# diodes.net
KiCad netlist of a schematic drawn in EAGLE
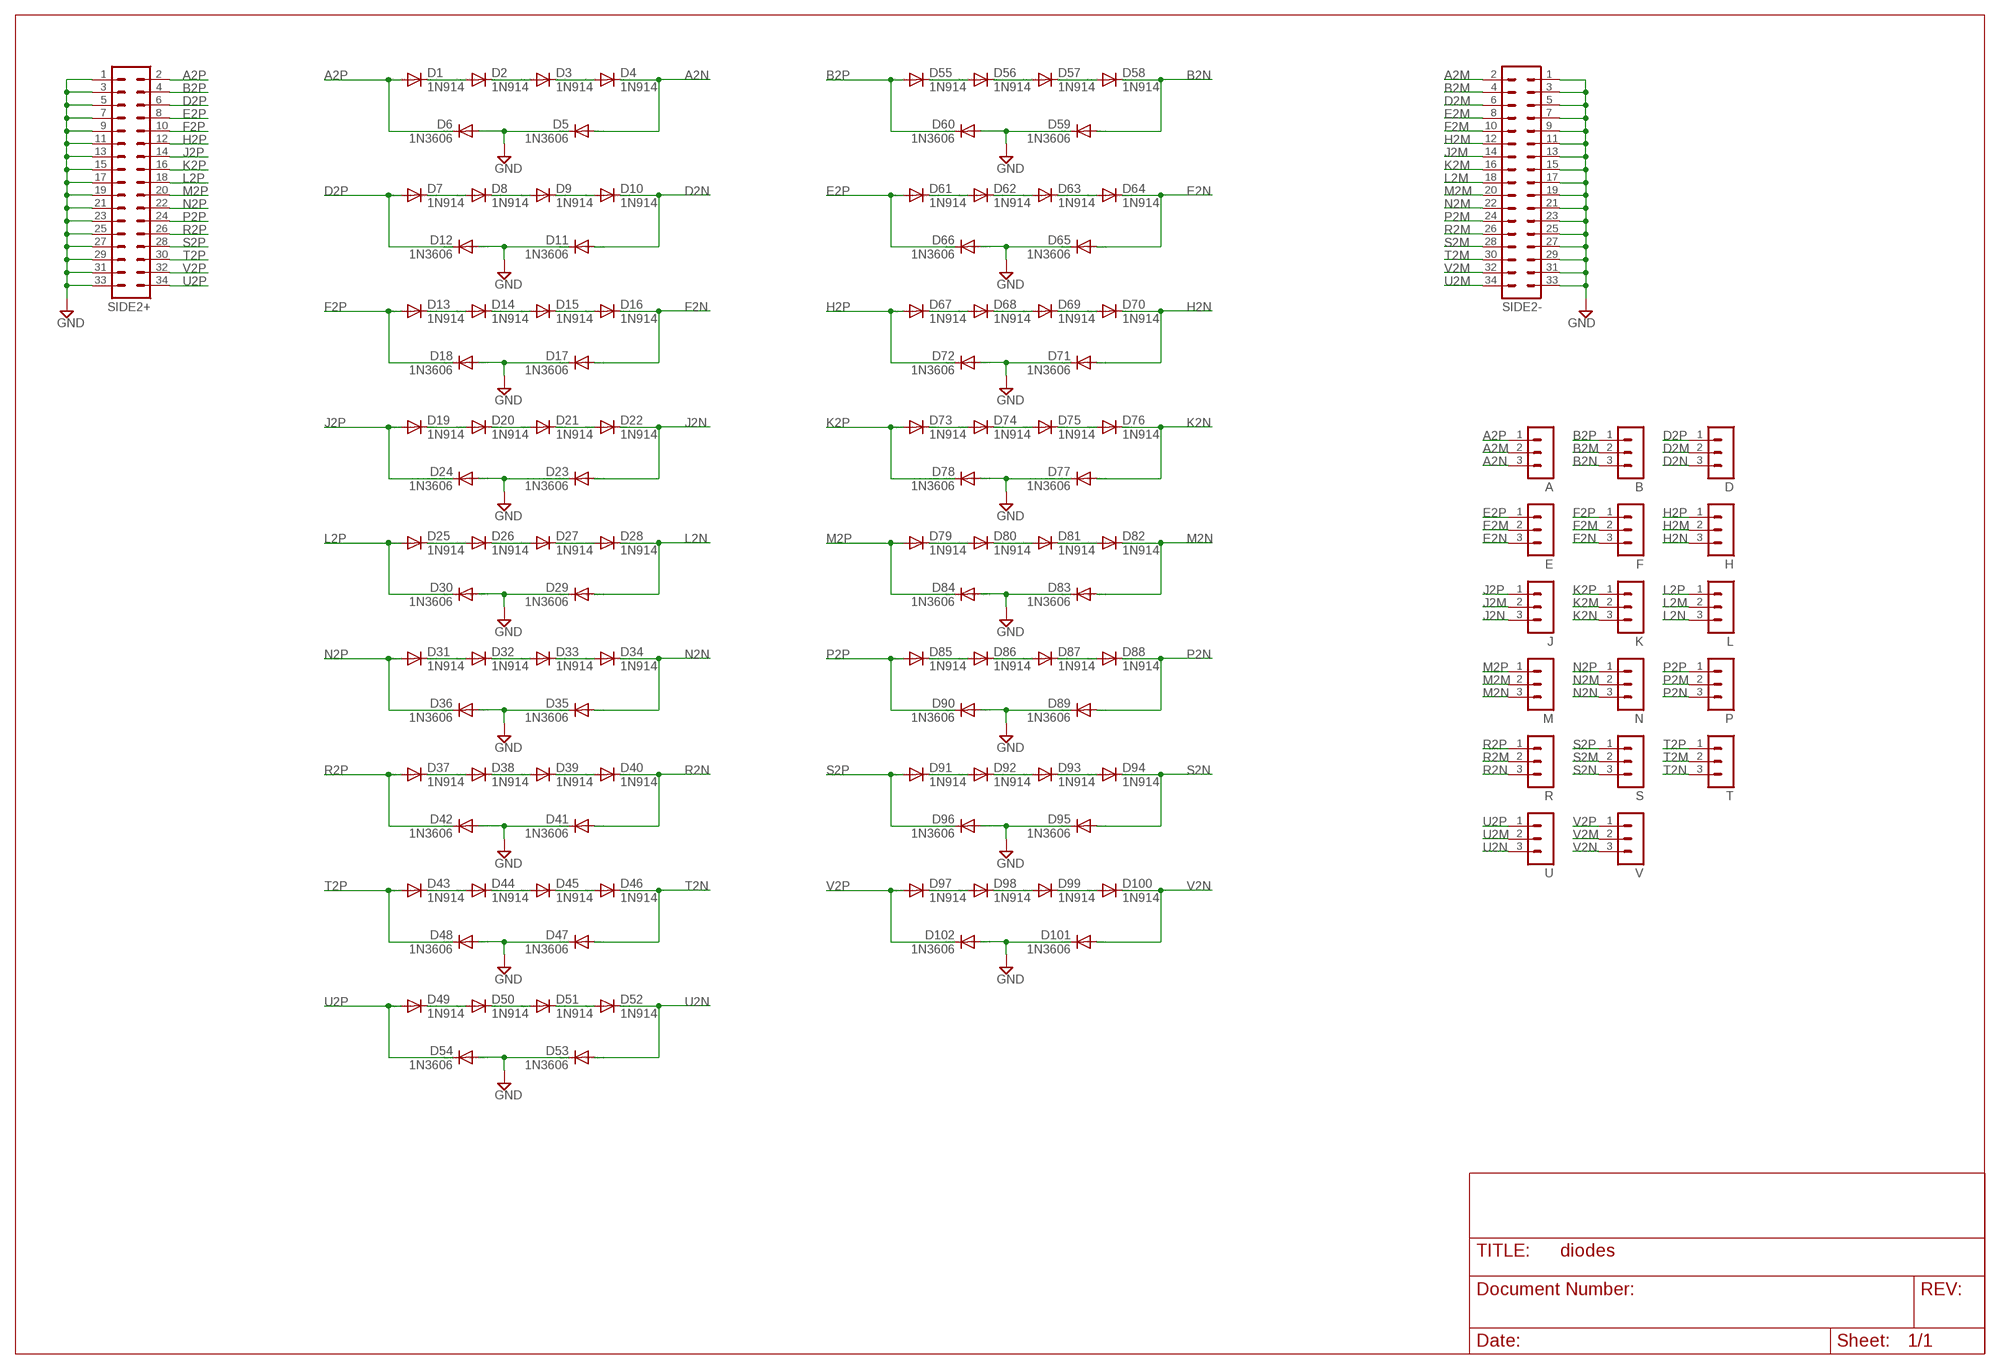
[diagram p0: schematic, sheet 1]

(export (version "E")
  (design (tool "Eeschema 10.0.6"))
  (components
    (comp (ref "A")
      (value "MA03-1")
      (footprint "eagle-import:MA03-1")
      (libsource (lib "eagle-import") (part "MA03-1"))
    )
    (comp (ref "B")
      (value "MA03-1")
      (footprint "eagle-import:MA03-1")
      (libsource (lib "eagle-import") (part "MA03-1"))
    )
    (comp (ref "D")
      (value "MA03-1")
      (footprint "eagle-import:MA03-1")
      (libsource (lib "eagle-import") (part "MA03-1"))
    )
    (comp (ref "D1")
      (value "1N914")
      (footprint "eagle-import:DO35-10")
      (libsource (lib "eagle-import") (part "DIODE-DO35-10"))
    )
    (comp (ref "D2")
      (value "1N914")
      (footprint "eagle-import:DO35-10")
      (libsource (lib "eagle-import") (part "DIODE-DO35-10"))
    )
    (comp (ref "D3")
      (value "1N914")
      (footprint "eagle-import:DO35-10")
      (libsource (lib "eagle-import") (part "DIODE-DO35-10"))
    )
    (comp (ref "D4")
      (value "1N914")
      (footprint "eagle-import:DO35-10")
      (libsource (lib "eagle-import") (part "DIODE-DO35-10"))
    )
    (comp (ref "D5")
      (value "1N3606")
      (footprint "eagle-import:DO35-10")
      (libsource (lib "eagle-import") (part "DIODE-DO35-10"))
    )
    (comp (ref "D6")
      (value "1N3606")
      (footprint "eagle-import:DO35-10")
      (libsource (lib "eagle-import") (part "DIODE-DO35-10"))
    )
    (comp (ref "D7")
      (value "1N914")
      (footprint "eagle-import:DO35-10")
      (libsource (lib "eagle-import") (part "DIODE-DO35-10"))
    )
    (comp (ref "D8")
      (value "1N914")
      (footprint "eagle-import:DO35-10")
      (libsource (lib "eagle-import") (part "DIODE-DO35-10"))
    )
    (comp (ref "D9")
      (value "1N914")
      (footprint "eagle-import:DO35-10")
      (libsource (lib "eagle-import") (part "DIODE-DO35-10"))
    )
    (comp (ref "D10")
      (value "1N914")
      (footprint "eagle-import:DO35-10")
      (libsource (lib "eagle-import") (part "DIODE-DO35-10"))
    )
    (comp (ref "D11")
      (value "1N3606")
      (footprint "eagle-import:DO35-10")
      (libsource (lib "eagle-import") (part "DIODE-DO35-10"))
    )
    (comp (ref "D12")
      (value "1N3606")
      (footprint "eagle-import:DO35-10")
      (libsource (lib "eagle-import") (part "DIODE-DO35-10"))
    )
    (comp (ref "D13")
      (value "1N914")
      (footprint "eagle-import:DO35-10")
      (libsource (lib "eagle-import") (part "DIODE-DO35-10"))
    )
    (comp (ref "D14")
      (value "1N914")
      (footprint "eagle-import:DO35-10")
      (libsource (lib "eagle-import") (part "DIODE-DO35-10"))
    )
    (comp (ref "D15")
      (value "1N914")
      (footprint "eagle-import:DO35-10")
      (libsource (lib "eagle-import") (part "DIODE-DO35-10"))
    )
    (comp (ref "D16")
      (value "1N914")
      (footprint "eagle-import:DO35-10")
      (libsource (lib "eagle-import") (part "DIODE-DO35-10"))
    )
    (comp (ref "D17")
      (value "1N3606")
      (footprint "eagle-import:DO35-10")
      (libsource (lib "eagle-import") (part "DIODE-DO35-10"))
    )
    (comp (ref "D18")
      (value "1N3606")
      (footprint "eagle-import:DO35-10")
      (libsource (lib "eagle-import") (part "DIODE-DO35-10"))
    )
    (comp (ref "D19")
      (value "1N914")
      (footprint "eagle-import:DO35-10")
      (libsource (lib "eagle-import") (part "DIODE-DO35-10"))
    )
    (comp (ref "D20")
      (value "1N914")
      (footprint "eagle-import:DO35-10")
      (libsource (lib "eagle-import") (part "DIODE-DO35-10"))
    )
    (comp (ref "D21")
      (value "1N914")
      (footprint "eagle-import:DO35-10")
      (libsource (lib "eagle-import") (part "DIODE-DO35-10"))
    )
    (comp (ref "D22")
      (value "1N914")
      (footprint "eagle-import:DO35-10")
      (libsource (lib "eagle-import") (part "DIODE-DO35-10"))
    )
    (comp (ref "D23")
      (value "1N3606")
      (footprint "eagle-import:DO35-10")
      (libsource (lib "eagle-import") (part "DIODE-DO35-10"))
    )
    (comp (ref "D24")
      (value "1N3606")
      (footprint "eagle-import:DO35-10")
      (libsource (lib "eagle-import") (part "DIODE-DO35-10"))
    )
    (comp (ref "D25")
      (value "1N914")
      (footprint "eagle-import:DO35-10")
      (libsource (lib "eagle-import") (part "DIODE-DO35-10"))
    )
    (comp (ref "D26")
      (value "1N914")
      (footprint "eagle-import:DO35-10")
      (libsource (lib "eagle-import") (part "DIODE-DO35-10"))
    )
    (comp (ref "D27")
      (value "1N914")
      (footprint "eagle-import:DO35-10")
      (libsource (lib "eagle-import") (part "DIODE-DO35-10"))
    )
    (comp (ref "D28")
      (value "1N914")
      (footprint "eagle-import:DO35-10")
      (libsource (lib "eagle-import") (part "DIODE-DO35-10"))
    )
    (comp (ref "D29")
      (value "1N3606")
      (footprint "eagle-import:DO35-10")
      (libsource (lib "eagle-import") (part "DIODE-DO35-10"))
    )
    (comp (ref "D30")
      (value "1N3606")
      (footprint "eagle-import:DO35-10")
      (libsource (lib "eagle-import") (part "DIODE-DO35-10"))
    )
    (comp (ref "D31")
      (value "1N914")
      (footprint "eagle-import:DO35-10")
      (libsource (lib "eagle-import") (part "DIODE-DO35-10"))
    )
    (comp (ref "D32")
      (value "1N914")
      (footprint "eagle-import:DO35-10")
      (libsource (lib "eagle-import") (part "DIODE-DO35-10"))
    )
    (comp (ref "D33")
      (value "1N914")
      (footprint "eagle-import:DO35-10")
      (libsource (lib "eagle-import") (part "DIODE-DO35-10"))
    )
    (comp (ref "D34")
      (value "1N914")
      (footprint "eagle-import:DO35-10")
      (libsource (lib "eagle-import") (part "DIODE-DO35-10"))
    )
    (comp (ref "D35")
      (value "1N3606")
      (footprint "eagle-import:DO35-10")
      (libsource (lib "eagle-import") (part "DIODE-DO35-10"))
    )
    (comp (ref "D36")
      (value "1N3606")
      (footprint "eagle-import:DO35-10")
      (libsource (lib "eagle-import") (part "DIODE-DO35-10"))
    )
    (comp (ref "D37")
      (value "1N914")
      (footprint "eagle-import:DO35-10")
      (libsource (lib "eagle-import") (part "DIODE-DO35-10"))
    )
    (comp (ref "D38")
      (value "1N914")
      (footprint "eagle-import:DO35-10")
      (libsource (lib "eagle-import") (part "DIODE-DO35-10"))
    )
    (comp (ref "D39")
      (value "1N914")
      (footprint "eagle-import:DO35-10")
      (libsource (lib "eagle-import") (part "DIODE-DO35-10"))
    )
    (comp (ref "D40")
      (value "1N914")
      (footprint "eagle-import:DO35-10")
      (libsource (lib "eagle-import") (part "DIODE-DO35-10"))
    )
    (comp (ref "D41")
      (value "1N3606")
      (footprint "eagle-import:DO35-10")
      (libsource (lib "eagle-import") (part "DIODE-DO35-10"))
    )
    (comp (ref "D42")
      (value "1N3606")
      (footprint "eagle-import:DO35-10")
      (libsource (lib "eagle-import") (part "DIODE-DO35-10"))
    )
    (comp (ref "D43")
      (value "1N914")
      (footprint "eagle-import:DO35-10")
      (libsource (lib "eagle-import") (part "DIODE-DO35-10"))
    )
    (comp (ref "D44")
      (value "1N914")
      (footprint "eagle-import:DO35-10")
      (libsource (lib "eagle-import") (part "DIODE-DO35-10"))
    )
    (comp (ref "D45")
      (value "1N914")
      (footprint "eagle-import:DO35-10")
      (libsource (lib "eagle-import") (part "DIODE-DO35-10"))
    )
    (comp (ref "D46")
      (value "1N914")
      (footprint "eagle-import:DO35-10")
      (libsource (lib "eagle-import") (part "DIODE-DO35-10"))
    )
    (comp (ref "D47")
      (value "1N3606")
      (footprint "eagle-import:DO35-10")
      (libsource (lib "eagle-import") (part "DIODE-DO35-10"))
    )
    (comp (ref "D48")
      (value "1N3606")
      (footprint "eagle-import:DO35-10")
      (libsource (lib "eagle-import") (part "DIODE-DO35-10"))
    )
    (comp (ref "D49")
      (value "1N914")
      (footprint "eagle-import:DO35-10")
      (libsource (lib "eagle-import") (part "DIODE-DO35-10"))
    )
    (comp (ref "D50")
      (value "1N914")
      (footprint "eagle-import:DO35-10")
      (libsource (lib "eagle-import") (part "DIODE-DO35-10"))
    )
    (comp (ref "D51")
      (value "1N914")
      (footprint "eagle-import:DO35-10")
      (libsource (lib "eagle-import") (part "DIODE-DO35-10"))
    )
    (comp (ref "D52")
      (value "1N914")
      (footprint "eagle-import:DO35-10")
      (libsource (lib "eagle-import") (part "DIODE-DO35-10"))
    )
    (comp (ref "D53")
      (value "1N3606")
      (footprint "eagle-import:DO35-10")
      (libsource (lib "eagle-import") (part "DIODE-DO35-10"))
    )
    (comp (ref "D54")
      (value "1N3606")
      (footprint "eagle-import:DO35-10")
      (libsource (lib "eagle-import") (part "DIODE-DO35-10"))
    )
    (comp (ref "D55")
      (value "1N914")
      (footprint "eagle-import:DO35-10")
      (libsource (lib "eagle-import") (part "DIODE-DO35-10"))
    )
    (comp (ref "D56")
      (value "1N914")
      (footprint "eagle-import:DO35-10")
      (libsource (lib "eagle-import") (part "DIODE-DO35-10"))
    )
    (comp (ref "D57")
      (value "1N914")
      (footprint "eagle-import:DO35-10")
      (libsource (lib "eagle-import") (part "DIODE-DO35-10"))
    )
    (comp (ref "D58")
      (value "1N914")
      (footprint "eagle-import:DO35-10")
      (libsource (lib "eagle-import") (part "DIODE-DO35-10"))
    )
    (comp (ref "D59")
      (value "1N3606")
      (footprint "eagle-import:DO35-10")
      (libsource (lib "eagle-import") (part "DIODE-DO35-10"))
    )
    (comp (ref "D60")
      (value "1N3606")
      (footprint "eagle-import:DO35-10")
      (libsource (lib "eagle-import") (part "DIODE-DO35-10"))
    )
    (comp (ref "D61")
      (value "1N914")
      (footprint "eagle-import:DO35-10")
      (libsource (lib "eagle-import") (part "DIODE-DO35-10"))
    )
    (comp (ref "D62")
      (value "1N914")
      (footprint "eagle-import:DO35-10")
      (libsource (lib "eagle-import") (part "DIODE-DO35-10"))
    )
    (comp (ref "D63")
      (value "1N914")
      (footprint "eagle-import:DO35-10")
      (libsource (lib "eagle-import") (part "DIODE-DO35-10"))
    )
    (comp (ref "D64")
      (value "1N914")
      (footprint "eagle-import:DO35-10")
      (libsource (lib "eagle-import") (part "DIODE-DO35-10"))
    )
    (comp (ref "D65")
      (value "1N3606")
      (footprint "eagle-import:DO35-10")
      (libsource (lib "eagle-import") (part "DIODE-DO35-10"))
    )
    (comp (ref "D66")
      (value "1N3606")
      (footprint "eagle-import:DO35-10")
      (libsource (lib "eagle-import") (part "DIODE-DO35-10"))
    )
    (comp (ref "D67")
      (value "1N914")
      (footprint "eagle-import:DO35-10")
      (libsource (lib "eagle-import") (part "DIODE-DO35-10"))
    )
    (comp (ref "D68")
      (value "1N914")
      (footprint "eagle-import:DO35-10")
      (libsource (lib "eagle-import") (part "DIODE-DO35-10"))
    )
    (comp (ref "D69")
      (value "1N914")
      (footprint "eagle-import:DO35-10")
      (libsource (lib "eagle-import") (part "DIODE-DO35-10"))
    )
    (comp (ref "D70")
      (value "1N914")
      (footprint "eagle-import:DO35-10")
      (libsource (lib "eagle-import") (part "DIODE-DO35-10"))
    )
    (comp (ref "D71")
      (value "1N3606")
      (footprint "eagle-import:DO35-10")
      (libsource (lib "eagle-import") (part "DIODE-DO35-10"))
    )
    (comp (ref "D72")
      (value "1N3606")
      (footprint "eagle-import:DO35-10")
      (libsource (lib "eagle-import") (part "DIODE-DO35-10"))
    )
    (comp (ref "D73")
      (value "1N914")
      (footprint "eagle-import:DO35-10")
      (libsource (lib "eagle-import") (part "DIODE-DO35-10"))
    )
    (comp (ref "D74")
      (value "1N914")
      (footprint "eagle-import:DO35-10")
      (libsource (lib "eagle-import") (part "DIODE-DO35-10"))
    )
    (comp (ref "D75")
      (value "1N914")
      (footprint "eagle-import:DO35-10")
      (libsource (lib "eagle-import") (part "DIODE-DO35-10"))
    )
    (comp (ref "D76")
      (value "1N914")
      (footprint "eagle-import:DO35-10")
      (libsource (lib "eagle-import") (part "DIODE-DO35-10"))
    )
    (comp (ref "D77")
      (value "1N3606")
      (footprint "eagle-import:DO35-10")
      (libsource (lib "eagle-import") (part "DIODE-DO35-10"))
    )
    (comp (ref "D78")
      (value "1N3606")
      (footprint "eagle-import:DO35-10")
      (libsource (lib "eagle-import") (part "DIODE-DO35-10"))
    )
    (comp (ref "D79")
      (value "1N914")
      (footprint "eagle-import:DO35-10")
      (libsource (lib "eagle-import") (part "DIODE-DO35-10"))
    )
    (comp (ref "D80")
      (value "1N914")
      (footprint "eagle-import:DO35-10")
      (libsource (lib "eagle-import") (part "DIODE-DO35-10"))
    )
    (comp (ref "D81")
      (value "1N914")
      (footprint "eagle-import:DO35-10")
      (libsource (lib "eagle-import") (part "DIODE-DO35-10"))
    )
    (comp (ref "D82")
      (value "1N914")
      (footprint "eagle-import:DO35-10")
      (libsource (lib "eagle-import") (part "DIODE-DO35-10"))
    )
    (comp (ref "D83")
      (value "1N3606")
      (footprint "eagle-import:DO35-10")
      (libsource (lib "eagle-import") (part "DIODE-DO35-10"))
    )
    (comp (ref "D84")
      (value "1N3606")
      (footprint "eagle-import:DO35-10")
      (libsource (lib "eagle-import") (part "DIODE-DO35-10"))
    )
    (comp (ref "D85")
      (value "1N914")
      (footprint "eagle-import:DO35-10")
      (libsource (lib "eagle-import") (part "DIODE-DO35-10"))
    )
    (comp (ref "D86")
      (value "1N914")
      (footprint "eagle-import:DO35-10")
      (libsource (lib "eagle-import") (part "DIODE-DO35-10"))
    )
    (comp (ref "D87")
      (value "1N914")
      (footprint "eagle-import:DO35-10")
      (libsource (lib "eagle-import") (part "DIODE-DO35-10"))
    )
    (comp (ref "D88")
      (value "1N914")
      (footprint "eagle-import:DO35-10")
      (libsource (lib "eagle-import") (part "DIODE-DO35-10"))
    )
    (comp (ref "D89")
      (value "1N3606")
      (footprint "eagle-import:DO35-10")
      (libsource (lib "eagle-import") (part "DIODE-DO35-10"))
    )
    (comp (ref "D90")
      (value "1N3606")
      (footprint "eagle-import:DO35-10")
      (libsource (lib "eagle-import") (part "DIODE-DO35-10"))
    )
    (comp (ref "D91")
      (value "1N914")
      (footprint "eagle-import:DO35-10")
      (libsource (lib "eagle-import") (part "DIODE-DO35-10"))
    )
    (comp (ref "D92")
      (value "1N914")
      (footprint "eagle-import:DO35-10")
      (libsource (lib "eagle-import") (part "DIODE-DO35-10"))
    )
    (comp (ref "D93")
      (value "1N914")
      (footprint "eagle-import:DO35-10")
      (libsource (lib "eagle-import") (part "DIODE-DO35-10"))
    )
    (comp (ref "D94")
      (value "1N914")
      (footprint "eagle-import:DO35-10")
      (libsource (lib "eagle-import") (part "DIODE-DO35-10"))
    )
    (comp (ref "D95")
      (value "1N3606")
      (footprint "eagle-import:DO35-10")
      (libsource (lib "eagle-import") (part "DIODE-DO35-10"))
    )
    (comp (ref "D96")
      (value "1N3606")
      (footprint "eagle-import:DO35-10")
      (libsource (lib "eagle-import") (part "DIODE-DO35-10"))
    )
    (comp (ref "D97")
      (value "1N914")
      (footprint "eagle-import:DO35-10")
      (libsource (lib "eagle-import") (part "DIODE-DO35-10"))
    )
    (comp (ref "D98")
      (value "1N914")
      (footprint "eagle-import:DO35-10")
      (libsource (lib "eagle-import") (part "DIODE-DO35-10"))
    )
    (comp (ref "D99")
      (value "1N914")
      (footprint "eagle-import:DO35-10")
      (libsource (lib "eagle-import") (part "DIODE-DO35-10"))
    )
    (comp (ref "D100")
      (value "1N914")
      (footprint "eagle-import:DO35-10")
      (libsource (lib "eagle-import") (part "DIODE-DO35-10"))
    )
    (comp (ref "D101")
      (value "1N3606")
      (footprint "eagle-import:DO35-10")
      (libsource (lib "eagle-import") (part "DIODE-DO35-10"))
    )
    (comp (ref "D102")
      (value "1N3606")
      (footprint "eagle-import:DO35-10")
      (libsource (lib "eagle-import") (part "DIODE-DO35-10"))
    )
    (comp (ref "E")
      (value "MA03-1")
      (footprint "eagle-import:MA03-1")
      (libsource (lib "eagle-import") (part "MA03-1"))
    )
    (comp (ref "F")
      (value "MA03-1")
      (footprint "eagle-import:MA03-1")
      (libsource (lib "eagle-import") (part "MA03-1"))
    )
    (comp (ref "H")
      (value "MA03-1")
      (footprint "eagle-import:MA03-1")
      (libsource (lib "eagle-import") (part "MA03-1"))
    )
    (comp (ref "J")
      (value "MA03-1")
      (footprint "eagle-import:MA03-1")
      (libsource (lib "eagle-import") (part "MA03-1"))
    )
    (comp (ref "K")
      (value "MA03-1")
      (footprint "eagle-import:MA03-1")
      (libsource (lib "eagle-import") (part "MA03-1"))
    )
    (comp (ref "L")
      (value "MA03-1")
      (footprint "eagle-import:MA03-1")
      (libsource (lib "eagle-import") (part "MA03-1"))
    )
    (comp (ref "M")
      (value "MA03-1")
      (footprint "eagle-import:MA03-1")
      (libsource (lib "eagle-import") (part "MA03-1"))
    )
    (comp (ref "N")
      (value "MA03-1")
      (footprint "eagle-import:MA03-1")
      (libsource (lib "eagle-import") (part "MA03-1"))
    )
    (comp (ref "P")
      (value "MA03-1")
      (footprint "eagle-import:MA03-1")
      (libsource (lib "eagle-import") (part "MA03-1"))
    )
    (comp (ref "R")
      (value "MA03-1")
      (footprint "eagle-import:MA03-1")
      (libsource (lib "eagle-import") (part "MA03-1"))
    )
    (comp (ref "S")
      (value "MA03-1")
      (footprint "eagle-import:MA03-1")
      (libsource (lib "eagle-import") (part "MA03-1"))
    )
    (comp (ref "SIDE2+")
      (value "MA17-2")
      (footprint "eagle-import:MA17-2")
      (libsource (lib "eagle-import") (part "MA17-2"))
    )
    (comp (ref "SIDE2-")
      (value "MA17-2")
      (footprint "eagle-import:MA17-2")
      (libsource (lib "eagle-import") (part "MA17-2"))
    )
    (comp (ref "T")
      (value "MA03-1")
      (footprint "eagle-import:MA03-1")
      (libsource (lib "eagle-import") (part "MA03-1"))
    )
    (comp (ref "U")
      (value "MA03-1")
      (footprint "eagle-import:MA03-1")
      (libsource (lib "eagle-import") (part "MA03-1"))
    )
    (comp (ref "V")
      (value "MA03-1")
      (footprint "eagle-import:MA03-1")
      (libsource (lib "eagle-import") (part "MA03-1"))
    )
  )
  (nets
    (net (code "1") (name "/A2M") (class "Default")
      (node (ref "A") (pin "2") (pinfunction "2_2") (pintype "passive"))
      (node (ref "SIDE2-") (pin "2") (pinfunction "2_2") (pintype "passive"))
    )
    (net (code "2") (name "/A2N") (class "Default")
      (node (ref "A") (pin "3") (pinfunction "3_3") (pintype "passive"))
      (node (ref "D4") (pin "C") (pinfunction "C_C") (pintype "passive"))
      (node (ref "D5") (pin "A") (pinfunction "A_A") (pintype "passive"))
    )
    (net (code "3") (name "/A2P") (class "Default")
      (node (ref "A") (pin "1") (pinfunction "1_1") (pintype "passive"))
      (node (ref "D1") (pin "A") (pinfunction "A_A") (pintype "passive"))
      (node (ref "D6") (pin "C") (pinfunction "C_C") (pintype "passive"))
      (node (ref "SIDE2+") (pin "2") (pinfunction "2_2") (pintype "passive"))
    )
    (net (code "4") (name "/B2M") (class "Default")
      (node (ref "B") (pin "2") (pinfunction "2_2") (pintype "passive"))
      (node (ref "SIDE2-") (pin "4") (pinfunction "4_4") (pintype "passive"))
    )
    (net (code "5") (name "/B2N") (class "Default")
      (node (ref "B") (pin "3") (pinfunction "3_3") (pintype "passive"))
      (node (ref "D58") (pin "C") (pinfunction "C_C") (pintype "passive"))
      (node (ref "D59") (pin "A") (pinfunction "A_A") (pintype "passive"))
    )
    (net (code "6") (name "/B2P") (class "Default")
      (node (ref "B") (pin "1") (pinfunction "1_1") (pintype "passive"))
      (node (ref "D55") (pin "A") (pinfunction "A_A") (pintype "passive"))
      (node (ref "D60") (pin "C") (pinfunction "C_C") (pintype "passive"))
      (node (ref "SIDE2+") (pin "4") (pinfunction "4_4") (pintype "passive"))
    )
    (net (code "7") (name "/D2M") (class "Default")
      (node (ref "D") (pin "2") (pinfunction "2_2") (pintype "passive"))
      (node (ref "SIDE2-") (pin "6") (pinfunction "6_6") (pintype "passive"))
    )
    (net (code "8") (name "/D2N") (class "Default")
      (node (ref "D") (pin "3") (pinfunction "3_3") (pintype "passive"))
      (node (ref "D10") (pin "C") (pinfunction "C_C") (pintype "passive"))
      (node (ref "D11") (pin "A") (pinfunction "A_A") (pintype "passive"))
    )
    (net (code "9") (name "/D2P") (class "Default")
      (node (ref "D") (pin "1") (pinfunction "1_1") (pintype "passive"))
      (node (ref "D12") (pin "C") (pinfunction "C_C") (pintype "passive"))
      (node (ref "D7") (pin "A") (pinfunction "A_A") (pintype "passive"))
      (node (ref "SIDE2+") (pin "6") (pinfunction "6_6") (pintype "passive"))
    )
    (net (code "10") (name "/E2M") (class "Default")
      (node (ref "E") (pin "2") (pinfunction "2_2") (pintype "passive"))
      (node (ref "SIDE2-") (pin "8") (pinfunction "8_8") (pintype "passive"))
    )
    (net (code "11") (name "/E2N") (class "Default")
      (node (ref "D64") (pin "C") (pinfunction "C_C") (pintype "passive"))
      (node (ref "D65") (pin "A") (pinfunction "A_A") (pintype "passive"))
      (node (ref "E") (pin "3") (pinfunction "3_3") (pintype "passive"))
    )
    (net (code "12") (name "/E2P") (class "Default")
      (node (ref "D61") (pin "A") (pinfunction "A_A") (pintype "passive"))
      (node (ref "D66") (pin "C") (pinfunction "C_C") (pintype "passive"))
      (node (ref "E") (pin "1") (pinfunction "1_1") (pintype "passive"))
      (node (ref "SIDE2+") (pin "8") (pinfunction "8_8") (pintype "passive"))
    )
    (net (code "13") (name "/F2M") (class "Default")
      (node (ref "F") (pin "2") (pinfunction "2_2") (pintype "passive"))
      (node (ref "SIDE2-") (pin "10") (pinfunction "10_10") (pintype "passive"))
    )
    (net (code "14") (name "/F2N") (class "Default")
      (node (ref "D16") (pin "C") (pinfunction "C_C") (pintype "passive"))
      (node (ref "D17") (pin "A") (pinfunction "A_A") (pintype "passive"))
      (node (ref "F") (pin "3") (pinfunction "3_3") (pintype "passive"))
    )
    (net (code "15") (name "/F2P") (class "Default")
      (node (ref "D13") (pin "A") (pinfunction "A_A") (pintype "passive"))
      (node (ref "D18") (pin "C") (pinfunction "C_C") (pintype "passive"))
      (node (ref "F") (pin "1") (pinfunction "1_1") (pintype "passive"))
      (node (ref "SIDE2+") (pin "10") (pinfunction "10_10") (pintype "passive"))
    )
    (net (code "16") (name "/H2M") (class "Default")
      (node (ref "H") (pin "2") (pinfunction "2_2") (pintype "passive"))
      (node (ref "SIDE2-") (pin "12") (pinfunction "12_12") (pintype "passive"))
    )
    (net (code "17") (name "/H2N") (class "Default")
      (node (ref "D70") (pin "C") (pinfunction "C_C") (pintype "passive"))
      (node (ref "D71") (pin "A") (pinfunction "A_A") (pintype "passive"))
      (node (ref "H") (pin "3") (pinfunction "3_3") (pintype "passive"))
    )
    (net (code "18") (name "/H2P") (class "Default")
      (node (ref "D67") (pin "A") (pinfunction "A_A") (pintype "passive"))
      (node (ref "D72") (pin "C") (pinfunction "C_C") (pintype "passive"))
      (node (ref "H") (pin "1") (pinfunction "1_1") (pintype "passive"))
      (node (ref "SIDE2+") (pin "12") (pinfunction "12_12") (pintype "passive"))
    )
    (net (code "19") (name "/J2M") (class "Default")
      (node (ref "J") (pin "2") (pinfunction "2_2") (pintype "passive"))
      (node (ref "SIDE2-") (pin "14") (pinfunction "14_14") (pintype "passive"))
    )
    (net (code "20") (name "/J2N") (class "Default")
      (node (ref "D22") (pin "C") (pinfunction "C_C") (pintype "passive"))
      (node (ref "D23") (pin "A") (pinfunction "A_A") (pintype "passive"))
      (node (ref "J") (pin "3") (pinfunction "3_3") (pintype "passive"))
    )
    (net (code "21") (name "/J2P") (class "Default")
      (node (ref "D19") (pin "A") (pinfunction "A_A") (pintype "passive"))
      (node (ref "D24") (pin "C") (pinfunction "C_C") (pintype "passive"))
      (node (ref "J") (pin "1") (pinfunction "1_1") (pintype "passive"))
      (node (ref "SIDE2+") (pin "14") (pinfunction "14_14") (pintype "passive"))
    )
    (net (code "22") (name "/K2M") (class "Default")
      (node (ref "K") (pin "2") (pinfunction "2_2") (pintype "passive"))
      (node (ref "SIDE2-") (pin "16") (pinfunction "16_16") (pintype "passive"))
    )
    (net (code "23") (name "/K2N") (class "Default")
      (node (ref "D76") (pin "C") (pinfunction "C_C") (pintype "passive"))
      (node (ref "D77") (pin "A") (pinfunction "A_A") (pintype "passive"))
      (node (ref "K") (pin "3") (pinfunction "3_3") (pintype "passive"))
    )
    (net (code "24") (name "/K2P") (class "Default")
      (node (ref "D73") (pin "A") (pinfunction "A_A") (pintype "passive"))
      (node (ref "D78") (pin "C") (pinfunction "C_C") (pintype "passive"))
      (node (ref "K") (pin "1") (pinfunction "1_1") (pintype "passive"))
      (node (ref "SIDE2+") (pin "16") (pinfunction "16_16") (pintype "passive"))
    )
    (net (code "25") (name "/L2M") (class "Default")
      (node (ref "L") (pin "2") (pinfunction "2_2") (pintype "passive"))
      (node (ref "SIDE2-") (pin "18") (pinfunction "18_18") (pintype "passive"))
    )
    (net (code "26") (name "/L2N") (class "Default")
      (node (ref "D28") (pin "C") (pinfunction "C_C") (pintype "passive"))
      (node (ref "D29") (pin "A") (pinfunction "A_A") (pintype "passive"))
      (node (ref "L") (pin "3") (pinfunction "3_3") (pintype "passive"))
    )
    (net (code "27") (name "/L2P") (class "Default")
      (node (ref "D25") (pin "A") (pinfunction "A_A") (pintype "passive"))
      (node (ref "D30") (pin "C") (pinfunction "C_C") (pintype "passive"))
      (node (ref "L") (pin "1") (pinfunction "1_1") (pintype "passive"))
      (node (ref "SIDE2+") (pin "18") (pinfunction "18_18") (pintype "passive"))
    )
    (net (code "28") (name "/M2M") (class "Default")
      (node (ref "M") (pin "2") (pinfunction "2_2") (pintype "passive"))
      (node (ref "SIDE2-") (pin "20") (pinfunction "20_20") (pintype "passive"))
    )
    (net (code "29") (name "/M2N") (class "Default")
      (node (ref "D82") (pin "C") (pinfunction "C_C") (pintype "passive"))
      (node (ref "D83") (pin "A") (pinfunction "A_A") (pintype "passive"))
      (node (ref "M") (pin "3") (pinfunction "3_3") (pintype "passive"))
    )
    (net (code "30") (name "/M2P") (class "Default")
      (node (ref "D79") (pin "A") (pinfunction "A_A") (pintype "passive"))
      (node (ref "D84") (pin "C") (pinfunction "C_C") (pintype "passive"))
      (node (ref "M") (pin "1") (pinfunction "1_1") (pintype "passive"))
      (node (ref "SIDE2+") (pin "20") (pinfunction "20_20") (pintype "passive"))
    )
    (net (code "31") (name "/N2M") (class "Default")
      (node (ref "N") (pin "2") (pinfunction "2_2") (pintype "passive"))
      (node (ref "SIDE2-") (pin "22") (pinfunction "22_22") (pintype "passive"))
    )
    (net (code "32") (name "/N2N") (class "Default")
      (node (ref "D34") (pin "C") (pinfunction "C_C") (pintype "passive"))
      (node (ref "D35") (pin "A") (pinfunction "A_A") (pintype "passive"))
      (node (ref "N") (pin "3") (pinfunction "3_3") (pintype "passive"))
    )
    (net (code "33") (name "/N2P") (class "Default")
      (node (ref "D31") (pin "A") (pinfunction "A_A") (pintype "passive"))
      (node (ref "D36") (pin "C") (pinfunction "C_C") (pintype "passive"))
      (node (ref "N") (pin "1") (pinfunction "1_1") (pintype "passive"))
      (node (ref "SIDE2+") (pin "22") (pinfunction "22_22") (pintype "passive"))
    )
    (net (code "34") (name "/P2M") (class "Default")
      (node (ref "P") (pin "2") (pinfunction "2_2") (pintype "passive"))
      (node (ref "SIDE2-") (pin "24") (pinfunction "24_24") (pintype "passive"))
    )
    (net (code "35") (name "/P2N") (class "Default")
      (node (ref "D88") (pin "C") (pinfunction "C_C") (pintype "passive"))
      (node (ref "D89") (pin "A") (pinfunction "A_A") (pintype "passive"))
      (node (ref "P") (pin "3") (pinfunction "3_3") (pintype "passive"))
    )
    (net (code "36") (name "/P2P") (class "Default")
      (node (ref "D85") (pin "A") (pinfunction "A_A") (pintype "passive"))
      (node (ref "D90") (pin "C") (pinfunction "C_C") (pintype "passive"))
      (node (ref "P") (pin "1") (pinfunction "1_1") (pintype "passive"))
      (node (ref "SIDE2+") (pin "24") (pinfunction "24_24") (pintype "passive"))
    )
    (net (code "37") (name "/R2M") (class "Default")
      (node (ref "R") (pin "2") (pinfunction "2_2") (pintype "passive"))
      (node (ref "SIDE2-") (pin "26") (pinfunction "26_26") (pintype "passive"))
    )
    (net (code "38") (name "/R2N") (class "Default")
      (node (ref "D40") (pin "C") (pinfunction "C_C") (pintype "passive"))
      (node (ref "D41") (pin "A") (pinfunction "A_A") (pintype "passive"))
      (node (ref "R") (pin "3") (pinfunction "3_3") (pintype "passive"))
    )
    (net (code "39") (name "/R2P") (class "Default")
      (node (ref "D37") (pin "A") (pinfunction "A_A") (pintype "passive"))
      (node (ref "D42") (pin "C") (pinfunction "C_C") (pintype "passive"))
      (node (ref "R") (pin "1") (pinfunction "1_1") (pintype "passive"))
      (node (ref "SIDE2+") (pin "26") (pinfunction "26_26") (pintype "passive"))
    )
    (net (code "40") (name "/S2M") (class "Default")
      (node (ref "S") (pin "2") (pinfunction "2_2") (pintype "passive"))
      (node (ref "SIDE2-") (pin "28") (pinfunction "28_28") (pintype "passive"))
    )
    (net (code "41") (name "/S2N") (class "Default")
      (node (ref "D94") (pin "C") (pinfunction "C_C") (pintype "passive"))
      (node (ref "D95") (pin "A") (pinfunction "A_A") (pintype "passive"))
      (node (ref "S") (pin "3") (pinfunction "3_3") (pintype "passive"))
    )
    (net (code "42") (name "/S2P") (class "Default")
      (node (ref "D91") (pin "A") (pinfunction "A_A") (pintype "passive"))
      (node (ref "D96") (pin "C") (pinfunction "C_C") (pintype "passive"))
      (node (ref "S") (pin "1") (pinfunction "1_1") (pintype "passive"))
      (node (ref "SIDE2+") (pin "28") (pinfunction "28_28") (pintype "passive"))
    )
    (net (code "43") (name "/T2M") (class "Default")
      (node (ref "SIDE2-") (pin "30") (pinfunction "30_30") (pintype "passive"))
      (node (ref "T") (pin "2") (pinfunction "2_2") (pintype "passive"))
    )
    (net (code "44") (name "/T2N") (class "Default")
      (node (ref "D46") (pin "C") (pinfunction "C_C") (pintype "passive"))
      (node (ref "D47") (pin "A") (pinfunction "A_A") (pintype "passive"))
      (node (ref "T") (pin "3") (pinfunction "3_3") (pintype "passive"))
    )
    (net (code "45") (name "/T2P") (class "Default")
      (node (ref "D43") (pin "A") (pinfunction "A_A") (pintype "passive"))
      (node (ref "D48") (pin "C") (pinfunction "C_C") (pintype "passive"))
      (node (ref "SIDE2+") (pin "30") (pinfunction "30_30") (pintype "passive"))
      (node (ref "T") (pin "1") (pinfunction "1_1") (pintype "passive"))
    )
    (net (code "46") (name "/U2M") (class "Default")
      (node (ref "SIDE2-") (pin "34") (pinfunction "34_34") (pintype "passive"))
      (node (ref "U") (pin "2") (pinfunction "2_2") (pintype "passive"))
    )
    (net (code "47") (name "/U2N") (class "Default")
      (node (ref "D52") (pin "C") (pinfunction "C_C") (pintype "passive"))
      (node (ref "D53") (pin "A") (pinfunction "A_A") (pintype "passive"))
      (node (ref "U") (pin "3") (pinfunction "3_3") (pintype "passive"))
    )
    (net (code "48") (name "/U2P") (class "Default")
      (node (ref "D49") (pin "A") (pinfunction "A_A") (pintype "passive"))
      (node (ref "D54") (pin "C") (pinfunction "C_C") (pintype "passive"))
      (node (ref "SIDE2+") (pin "34") (pinfunction "34_34") (pintype "passive"))
      (node (ref "U") (pin "1") (pinfunction "1_1") (pintype "passive"))
    )
    (net (code "49") (name "/V2M") (class "Default")
      (node (ref "SIDE2-") (pin "32") (pinfunction "32_32") (pintype "passive"))
      (node (ref "V") (pin "2") (pinfunction "2_2") (pintype "passive"))
    )
    (net (code "50") (name "/V2N") (class "Default")
      (node (ref "D100") (pin "C") (pinfunction "C_C") (pintype "passive"))
      (node (ref "D101") (pin "A") (pinfunction "A_A") (pintype "passive"))
      (node (ref "V") (pin "3") (pinfunction "3_3") (pintype "passive"))
    )
    (net (code "51") (name "/V2P") (class "Default")
      (node (ref "D102") (pin "C") (pinfunction "C_C") (pintype "passive"))
      (node (ref "D97") (pin "A") (pinfunction "A_A") (pintype "passive"))
      (node (ref "SIDE2+") (pin "32") (pinfunction "32_32") (pintype "passive"))
      (node (ref "V") (pin "1") (pinfunction "1_1") (pintype "passive"))
    )
    (net (code "52") (name "GND") (class "Default")
      (node (ref "D101") (pin "C") (pinfunction "C_C") (pintype "passive"))
      (node (ref "D102") (pin "A") (pinfunction "A_A") (pintype "passive"))
      (node (ref "D11") (pin "C") (pinfunction "C_C") (pintype "passive"))
      (node (ref "D12") (pin "A") (pinfunction "A_A") (pintype "passive"))
      (node (ref "D17") (pin "C") (pinfunction "C_C") (pintype "passive"))
      (node (ref "D18") (pin "A") (pinfunction "A_A") (pintype "passive"))
      (node (ref "D23") (pin "C") (pinfunction "C_C") (pintype "passive"))
      (node (ref "D24") (pin "A") (pinfunction "A_A") (pintype "passive"))
      (node (ref "D29") (pin "C") (pinfunction "C_C") (pintype "passive"))
      (node (ref "D30") (pin "A") (pinfunction "A_A") (pintype "passive"))
      (node (ref "D35") (pin "C") (pinfunction "C_C") (pintype "passive"))
      (node (ref "D36") (pin "A") (pinfunction "A_A") (pintype "passive"))
      (node (ref "D41") (pin "C") (pinfunction "C_C") (pintype "passive"))
      (node (ref "D42") (pin "A") (pinfunction "A_A") (pintype "passive"))
      (node (ref "D47") (pin "C") (pinfunction "C_C") (pintype "passive"))
      (node (ref "D48") (pin "A") (pinfunction "A_A") (pintype "passive"))
      (node (ref "D5") (pin "C") (pinfunction "C_C") (pintype "passive"))
      (node (ref "D53") (pin "C") (pinfunction "C_C") (pintype "passive"))
      (node (ref "D54") (pin "A") (pinfunction "A_A") (pintype "passive"))
      (node (ref "D59") (pin "C") (pinfunction "C_C") (pintype "passive"))
      (node (ref "D6") (pin "A") (pinfunction "A_A") (pintype "passive"))
      (node (ref "D60") (pin "A") (pinfunction "A_A") (pintype "passive"))
      (node (ref "D65") (pin "C") (pinfunction "C_C") (pintype "passive"))
      (node (ref "D66") (pin "A") (pinfunction "A_A") (pintype "passive"))
      (node (ref "D71") (pin "C") (pinfunction "C_C") (pintype "passive"))
      (node (ref "D72") (pin "A") (pinfunction "A_A") (pintype "passive"))
      (node (ref "D77") (pin "C") (pinfunction "C_C") (pintype "passive"))
      (node (ref "D78") (pin "A") (pinfunction "A_A") (pintype "passive"))
      (node (ref "D83") (pin "C") (pinfunction "C_C") (pintype "passive"))
      (node (ref "D84") (pin "A") (pinfunction "A_A") (pintype "passive"))
      (node (ref "D89") (pin "C") (pinfunction "C_C") (pintype "passive"))
      (node (ref "D90") (pin "A") (pinfunction "A_A") (pintype "passive"))
      (node (ref "D95") (pin "C") (pinfunction "C_C") (pintype "passive"))
      (node (ref "D96") (pin "A") (pinfunction "A_A") (pintype "passive"))
      (node (ref "SIDE2+") (pin "1") (pinfunction "1_1") (pintype "passive"))
      (node (ref "SIDE2+") (pin "11") (pinfunction "11_11") (pintype "passive"))
      (node (ref "SIDE2+") (pin "13") (pinfunction "13_13") (pintype "passive"))
      (node (ref "SIDE2+") (pin "15") (pinfunction "15_15") (pintype "passive"))
      (node (ref "SIDE2+") (pin "17") (pinfunction "17_17") (pintype "passive"))
      (node (ref "SIDE2+") (pin "19") (pinfunction "19_19") (pintype "passive"))
      (node (ref "SIDE2+") (pin "21") (pinfunction "21_21") (pintype "passive"))
      (node (ref "SIDE2+") (pin "23") (pinfunction "23_23") (pintype "passive"))
      (node (ref "SIDE2+") (pin "25") (pinfunction "25_25") (pintype "passive"))
      (node (ref "SIDE2+") (pin "27") (pinfunction "27_27") (pintype "passive"))
      (node (ref "SIDE2+") (pin "29") (pinfunction "29_29") (pintype "passive"))
      (node (ref "SIDE2+") (pin "3") (pinfunction "3_3") (pintype "passive"))
      (node (ref "SIDE2+") (pin "31") (pinfunction "31_31") (pintype "passive"))
      (node (ref "SIDE2+") (pin "33") (pinfunction "33_33") (pintype "passive"))
      (node (ref "SIDE2+") (pin "5") (pinfunction "5_5") (pintype "passive"))
      (node (ref "SIDE2+") (pin "7") (pinfunction "7_7") (pintype "passive"))
      (node (ref "SIDE2+") (pin "9") (pinfunction "9_9") (pintype "passive"))
      (node (ref "SIDE2-") (pin "1") (pinfunction "1_1") (pintype "passive"))
      (node (ref "SIDE2-") (pin "11") (pinfunction "11_11") (pintype "passive"))
      (node (ref "SIDE2-") (pin "13") (pinfunction "13_13") (pintype "passive"))
      (node (ref "SIDE2-") (pin "15") (pinfunction "15_15") (pintype "passive"))
      (node (ref "SIDE2-") (pin "17") (pinfunction "17_17") (pintype "passive"))
      (node (ref "SIDE2-") (pin "19") (pinfunction "19_19") (pintype "passive"))
      (node (ref "SIDE2-") (pin "21") (pinfunction "21_21") (pintype "passive"))
      (node (ref "SIDE2-") (pin "23") (pinfunction "23_23") (pintype "passive"))
      (node (ref "SIDE2-") (pin "25") (pinfunction "25_25") (pintype "passive"))
      (node (ref "SIDE2-") (pin "27") (pinfunction "27_27") (pintype "passive"))
      (node (ref "SIDE2-") (pin "29") (pinfunction "29_29") (pintype "passive"))
      (node (ref "SIDE2-") (pin "3") (pinfunction "3_3") (pintype "passive"))
      (node (ref "SIDE2-") (pin "31") (pinfunction "31_31") (pintype "passive"))
      (node (ref "SIDE2-") (pin "33") (pinfunction "33_33") (pintype "passive"))
      (node (ref "SIDE2-") (pin "5") (pinfunction "5_5") (pintype "passive"))
      (node (ref "SIDE2-") (pin "7") (pinfunction "7_7") (pintype "passive"))
      (node (ref "SIDE2-") (pin "9") (pinfunction "9_9") (pintype "passive"))
    )
    (net (code "53") (name "Net-(D1-PadC)") (class "Default")
      (node (ref "D1") (pin "C") (pinfunction "C_C") (pintype "passive"))
      (node (ref "D2") (pin "A") (pinfunction "A_A") (pintype "passive"))
    )
    (net (code "54") (name "Net-(D2-PadC)") (class "Default")
      (node (ref "D2") (pin "C") (pinfunction "C_C") (pintype "passive"))
      (node (ref "D3") (pin "A") (pinfunction "A_A") (pintype "passive"))
    )
    (net (code "55") (name "Net-(D3-PadC)") (class "Default")
      (node (ref "D3") (pin "C") (pinfunction "C_C") (pintype "passive"))
      (node (ref "D4") (pin "A") (pinfunction "A_A") (pintype "passive"))
    )
    (net (code "56") (name "Net-(D7-PadC)") (class "Default")
      (node (ref "D7") (pin "C") (pinfunction "C_C") (pintype "passive"))
      (node (ref "D8") (pin "A") (pinfunction "A_A") (pintype "passive"))
    )
    (net (code "57") (name "Net-(D8-PadC)") (class "Default")
      (node (ref "D8") (pin "C") (pinfunction "C_C") (pintype "passive"))
      (node (ref "D9") (pin "A") (pinfunction "A_A") (pintype "passive"))
    )
    (net (code "58") (name "Net-(D10-PadA)") (class "Default")
      (node (ref "D10") (pin "A") (pinfunction "A_A") (pintype "passive"))
      (node (ref "D9") (pin "C") (pinfunction "C_C") (pintype "passive"))
    )
    (net (code "59") (name "Net-(D13-PadC)") (class "Default")
      (node (ref "D13") (pin "C") (pinfunction "C_C") (pintype "passive"))
      (node (ref "D14") (pin "A") (pinfunction "A_A") (pintype "passive"))
    )
    (net (code "60") (name "Net-(D14-PadC)") (class "Default")
      (node (ref "D14") (pin "C") (pinfunction "C_C") (pintype "passive"))
      (node (ref "D15") (pin "A") (pinfunction "A_A") (pintype "passive"))
    )
    (net (code "61") (name "Net-(D15-PadC)") (class "Default")
      (node (ref "D15") (pin "C") (pinfunction "C_C") (pintype "passive"))
      (node (ref "D16") (pin "A") (pinfunction "A_A") (pintype "passive"))
    )
    (net (code "62") (name "Net-(D19-PadC)") (class "Default")
      (node (ref "D19") (pin "C") (pinfunction "C_C") (pintype "passive"))
      (node (ref "D20") (pin "A") (pinfunction "A_A") (pintype "passive"))
    )
    (net (code "63") (name "Net-(D20-PadC)") (class "Default")
      (node (ref "D20") (pin "C") (pinfunction "C_C") (pintype "passive"))
      (node (ref "D21") (pin "A") (pinfunction "A_A") (pintype "passive"))
    )
    (net (code "64") (name "Net-(D21-PadC)") (class "Default")
      (node (ref "D21") (pin "C") (pinfunction "C_C") (pintype "passive"))
      (node (ref "D22") (pin "A") (pinfunction "A_A") (pintype "passive"))
    )
    (net (code "65") (name "Net-(D25-PadC)") (class "Default")
      (node (ref "D25") (pin "C") (pinfunction "C_C") (pintype "passive"))
      (node (ref "D26") (pin "A") (pinfunction "A_A") (pintype "passive"))
    )
    (net (code "66") (name "Net-(D26-PadC)") (class "Default")
      (node (ref "D26") (pin "C") (pinfunction "C_C") (pintype "passive"))
      (node (ref "D27") (pin "A") (pinfunction "A_A") (pintype "passive"))
    )
    (net (code "67") (name "Net-(D27-PadC)") (class "Default")
      (node (ref "D27") (pin "C") (pinfunction "C_C") (pintype "passive"))
      (node (ref "D28") (pin "A") (pinfunction "A_A") (pintype "passive"))
    )
    (net (code "68") (name "Net-(D31-PadC)") (class "Default")
      (node (ref "D31") (pin "C") (pinfunction "C_C") (pintype "passive"))
      (node (ref "D32") (pin "A") (pinfunction "A_A") (pintype "passive"))
    )
    (net (code "69") (name "Net-(D32-PadC)") (class "Default")
      (node (ref "D32") (pin "C") (pinfunction "C_C") (pintype "passive"))
      (node (ref "D33") (pin "A") (pinfunction "A_A") (pintype "passive"))
    )
    (net (code "70") (name "Net-(D33-PadC)") (class "Default")
      (node (ref "D33") (pin "C") (pinfunction "C_C") (pintype "passive"))
      (node (ref "D34") (pin "A") (pinfunction "A_A") (pintype "passive"))
    )
    (net (code "71") (name "Net-(D37-PadC)") (class "Default")
      (node (ref "D37") (pin "C") (pinfunction "C_C") (pintype "passive"))
      (node (ref "D38") (pin "A") (pinfunction "A_A") (pintype "passive"))
    )
    (net (code "72") (name "Net-(D38-PadC)") (class "Default")
      (node (ref "D38") (pin "C") (pinfunction "C_C") (pintype "passive"))
      (node (ref "D39") (pin "A") (pinfunction "A_A") (pintype "passive"))
    )
    (net (code "73") (name "Net-(D39-PadC)") (class "Default")
      (node (ref "D39") (pin "C") (pinfunction "C_C") (pintype "passive"))
      (node (ref "D40") (pin "A") (pinfunction "A_A") (pintype "passive"))
    )
    (net (code "74") (name "Net-(D43-PadC)") (class "Default")
      (node (ref "D43") (pin "C") (pinfunction "C_C") (pintype "passive"))
      (node (ref "D44") (pin "A") (pinfunction "A_A") (pintype "passive"))
    )
    (net (code "75") (name "Net-(D44-PadC)") (class "Default")
      (node (ref "D44") (pin "C") (pinfunction "C_C") (pintype "passive"))
      (node (ref "D45") (pin "A") (pinfunction "A_A") (pintype "passive"))
    )
    (net (code "76") (name "Net-(D45-PadC)") (class "Default")
      (node (ref "D45") (pin "C") (pinfunction "C_C") (pintype "passive"))
      (node (ref "D46") (pin "A") (pinfunction "A_A") (pintype "passive"))
    )
    (net (code "77") (name "Net-(D49-PadC)") (class "Default")
      (node (ref "D49") (pin "C") (pinfunction "C_C") (pintype "passive"))
      (node (ref "D50") (pin "A") (pinfunction "A_A") (pintype "passive"))
    )
    (net (code "78") (name "Net-(D50-PadC)") (class "Default")
      (node (ref "D50") (pin "C") (pinfunction "C_C") (pintype "passive"))
      (node (ref "D51") (pin "A") (pinfunction "A_A") (pintype "passive"))
    )
    (net (code "79") (name "Net-(D51-PadC)") (class "Default")
      (node (ref "D51") (pin "C") (pinfunction "C_C") (pintype "passive"))
      (node (ref "D52") (pin "A") (pinfunction "A_A") (pintype "passive"))
    )
    (net (code "80") (name "Net-(D55-PadC)") (class "Default")
      (node (ref "D55") (pin "C") (pinfunction "C_C") (pintype "passive"))
      (node (ref "D56") (pin "A") (pinfunction "A_A") (pintype "passive"))
    )
    (net (code "81") (name "Net-(D56-PadC)") (class "Default")
      (node (ref "D56") (pin "C") (pinfunction "C_C") (pintype "passive"))
      (node (ref "D57") (pin "A") (pinfunction "A_A") (pintype "passive"))
    )
    (net (code "82") (name "Net-(D57-PadC)") (class "Default")
      (node (ref "D57") (pin "C") (pinfunction "C_C") (pintype "passive"))
      (node (ref "D58") (pin "A") (pinfunction "A_A") (pintype "passive"))
    )
    (net (code "83") (name "Net-(D61-PadC)") (class "Default")
      (node (ref "D61") (pin "C") (pinfunction "C_C") (pintype "passive"))
      (node (ref "D62") (pin "A") (pinfunction "A_A") (pintype "passive"))
    )
    (net (code "84") (name "Net-(D62-PadC)") (class "Default")
      (node (ref "D62") (pin "C") (pinfunction "C_C") (pintype "passive"))
      (node (ref "D63") (pin "A") (pinfunction "A_A") (pintype "passive"))
    )
    (net (code "85") (name "Net-(D63-PadC)") (class "Default")
      (node (ref "D63") (pin "C") (pinfunction "C_C") (pintype "passive"))
      (node (ref "D64") (pin "A") (pinfunction "A_A") (pintype "passive"))
    )
    (net (code "86") (name "Net-(D67-PadC)") (class "Default")
      (node (ref "D67") (pin "C") (pinfunction "C_C") (pintype "passive"))
      (node (ref "D68") (pin "A") (pinfunction "A_A") (pintype "passive"))
    )
    (net (code "87") (name "Net-(D68-PadC)") (class "Default")
      (node (ref "D68") (pin "C") (pinfunction "C_C") (pintype "passive"))
      (node (ref "D69") (pin "A") (pinfunction "A_A") (pintype "passive"))
    )
    (net (code "88") (name "Net-(D69-PadC)") (class "Default")
      (node (ref "D69") (pin "C") (pinfunction "C_C") (pintype "passive"))
      (node (ref "D70") (pin "A") (pinfunction "A_A") (pintype "passive"))
    )
    (net (code "89") (name "Net-(D73-PadC)") (class "Default")
      (node (ref "D73") (pin "C") (pinfunction "C_C") (pintype "passive"))
      (node (ref "D74") (pin "A") (pinfunction "A_A") (pintype "passive"))
    )
    (net (code "90") (name "Net-(D74-PadC)") (class "Default")
      (node (ref "D74") (pin "C") (pinfunction "C_C") (pintype "passive"))
      (node (ref "D75") (pin "A") (pinfunction "A_A") (pintype "passive"))
    )
    (net (code "91") (name "Net-(D75-PadC)") (class "Default")
      (node (ref "D75") (pin "C") (pinfunction "C_C") (pintype "passive"))
      (node (ref "D76") (pin "A") (pinfunction "A_A") (pintype "passive"))
    )
    (net (code "92") (name "Net-(D79-PadC)") (class "Default")
      (node (ref "D79") (pin "C") (pinfunction "C_C") (pintype "passive"))
      (node (ref "D80") (pin "A") (pinfunction "A_A") (pintype "passive"))
    )
    (net (code "93") (name "Net-(D80-PadC)") (class "Default")
      (node (ref "D80") (pin "C") (pinfunction "C_C") (pintype "passive"))
      (node (ref "D81") (pin "A") (pinfunction "A_A") (pintype "passive"))
    )
    (net (code "94") (name "Net-(D81-PadC)") (class "Default")
      (node (ref "D81") (pin "C") (pinfunction "C_C") (pintype "passive"))
      (node (ref "D82") (pin "A") (pinfunction "A_A") (pintype "passive"))
    )
    (net (code "95") (name "Net-(D85-PadC)") (class "Default")
      (node (ref "D85") (pin "C") (pinfunction "C_C") (pintype "passive"))
      (node (ref "D86") (pin "A") (pinfunction "A_A") (pintype "passive"))
    )
    (net (code "96") (name "Net-(D86-PadC)") (class "Default")
      (node (ref "D86") (pin "C") (pinfunction "C_C") (pintype "passive"))
      (node (ref "D87") (pin "A") (pinfunction "A_A") (pintype "passive"))
    )
    (net (code "97") (name "Net-(D87-PadC)") (class "Default")
      (node (ref "D87") (pin "C") (pinfunction "C_C") (pintype "passive"))
      (node (ref "D88") (pin "A") (pinfunction "A_A") (pintype "passive"))
    )
    (net (code "98") (name "Net-(D91-PadC)") (class "Default")
      (node (ref "D91") (pin "C") (pinfunction "C_C") (pintype "passive"))
      (node (ref "D92") (pin "A") (pinfunction "A_A") (pintype "passive"))
    )
    (net (code "99") (name "Net-(D92-PadC)") (class "Default")
      (node (ref "D92") (pin "C") (pinfunction "C_C") (pintype "passive"))
      (node (ref "D93") (pin "A") (pinfunction "A_A") (pintype "passive"))
    )
    (net (code "100") (name "Net-(D93-PadC)") (class "Default")
      (node (ref "D93") (pin "C") (pinfunction "C_C") (pintype "passive"))
      (node (ref "D94") (pin "A") (pinfunction "A_A") (pintype "passive"))
    )
    (net (code "101") (name "Net-(D97-PadC)") (class "Default")
      (node (ref "D97") (pin "C") (pinfunction "C_C") (pintype "passive"))
      (node (ref "D98") (pin "A") (pinfunction "A_A") (pintype "passive"))
    )
    (net (code "102") (name "Net-(D98-PadC)") (class "Default")
      (node (ref "D98") (pin "C") (pinfunction "C_C") (pintype "passive"))
      (node (ref "D99") (pin "A") (pinfunction "A_A") (pintype "passive"))
    )
    (net (code "103") (name "Net-(D100-PadA)") (class "Default")
      (node (ref "D100") (pin "A") (pinfunction "A_A") (pintype "passive"))
      (node (ref "D99") (pin "C") (pinfunction "C_C") (pintype "passive"))
    )
  )
)
